# hackeeg-connector-12.net
KiCad netlist of a schematic drawn in EAGLE
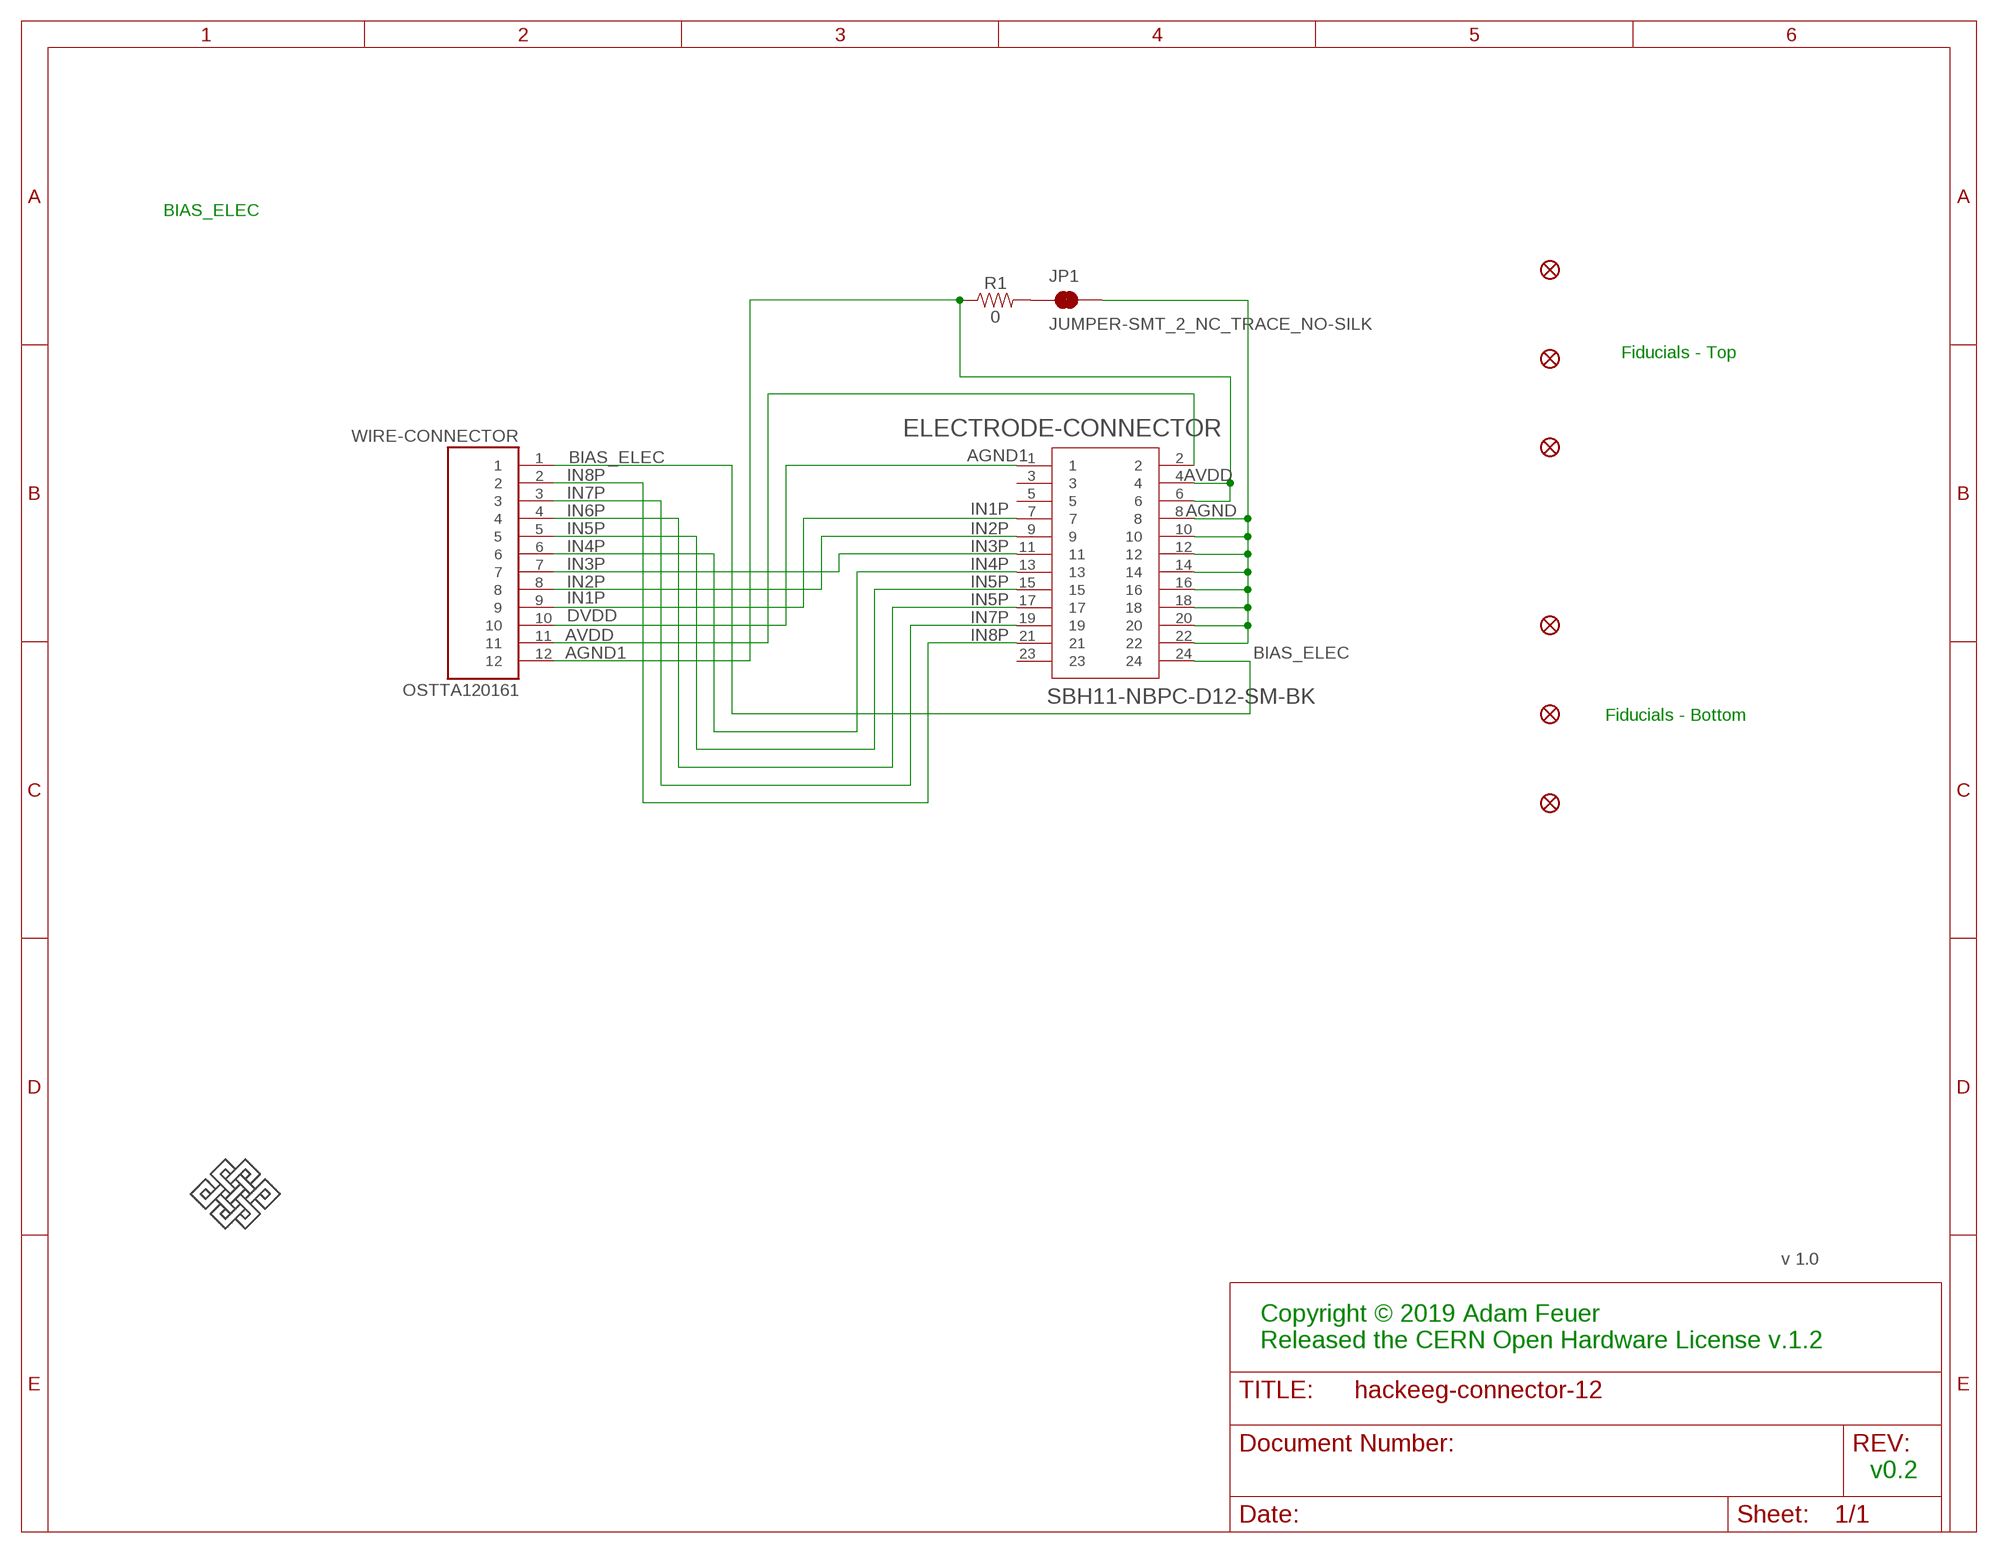
[diagram p0: schematic, sheet 1]

(export (version "E")
  (design (tool "Eeschema 10.0.6"))
  (components
    (comp (ref "ELECTRODE-CONNECTOR")
      (value "SBH11-NBPC-D12-SM-BK")
      (footprint "eagle-import:SULLINS_SBH11-NBPC-D12-SM-BK")
      (fields (field (name "MF") "Sullins Connector"))
      (libsource (lib "eagle-import") (part "SBH11-NBPC-D12-SM-BK"))
    )
    (comp (ref "FD1")
      (value "FIDUCIAL1X2")
      (footprint "eagle-import:FIDUCIAL-1X2")
      (libsource (lib "eagle-import") (part "FIDUCIAL1X2"))
    )
    (comp (ref "FD2")
      (value "FIDUCIAL1X2")
      (footprint "eagle-import:FIDUCIAL-1X2")
      (libsource (lib "eagle-import") (part "FIDUCIAL1X2"))
    )
    (comp (ref "FD3")
      (value "FIDUCIAL1X2")
      (footprint "eagle-import:FIDUCIAL-1X2")
      (libsource (lib "eagle-import") (part "FIDUCIAL1X2"))
    )
    (comp (ref "FD4")
      (value "FIDUCIAL1X2")
      (footprint "eagle-import:FIDUCIAL-1X2")
      (libsource (lib "eagle-import") (part "FIDUCIAL1X2"))
    )
    (comp (ref "FD5")
      (value "FIDUCIAL1X2")
      (footprint "eagle-import:FIDUCIAL-1X2")
      (libsource (lib "eagle-import") (part "FIDUCIAL1X2"))
    )
    (comp (ref "FD6")
      (value "FIDUCIAL1X2")
      (footprint "eagle-import:FIDUCIAL-1X2")
      (libsource (lib "eagle-import") (part "FIDUCIAL1X2"))
    )
    (comp (ref "JP1")
      (value "JUMPER-SMT_2_NC_TRACE_NO-SILK")
      (footprint "eagle-import:SMT-JUMPER_2_NC_TRACE_NO-SILK")
      (libsource (lib "eagle-import") (part "JUMPER-SMT_2_NC_TRACE_NO-SILK"))
    )
    (comp (ref "R1")
      (value "0")
      (footprint "eagle-import:0603")
      (libsource (lib "eagle-import") (part "0OHM-0603-1/10W-5%"))
    )
    (comp (ref "U$1")
      (value "ENDLESSKNOTENDLESSKNOT-MEDIUM")
      (footprint "eagle-import:ENDLESSKNOT-MEDIUM")
      (libsource (lib "eagle-import") (part "ENDLESSKNOTENDLESSKNOT-MEDIUM"))
    )
    (comp (ref "WIRE-CONNECTOR")
      (value "OSTTA120161")
      (footprint "eagle-import:ONSHORE_OSTTA120161")
      (fields (field (name "MF") "On Shore Technology Inc.") (field (name "MP") "OSTTA120161B"))
      (libsource (lib "eagle-import") (part "OSTTA120161"))
    )
  )
  (nets
    (net (code "1") (name "/AGND") (class "Default")
      (node (ref "ELECTRODE-CONNECTOR") (pin "10") (pinfunction "10_10") (pintype "passive"))
      (node (ref "ELECTRODE-CONNECTOR") (pin "12") (pinfunction "12_12") (pintype "passive"))
      (node (ref "ELECTRODE-CONNECTOR") (pin "14") (pinfunction "14_14") (pintype "passive"))
      (node (ref "ELECTRODE-CONNECTOR") (pin "16") (pinfunction "16_16") (pintype "passive"))
      (node (ref "ELECTRODE-CONNECTOR") (pin "18") (pinfunction "18_18") (pintype "passive"))
      (node (ref "ELECTRODE-CONNECTOR") (pin "20") (pinfunction "20_20") (pintype "passive"))
      (node (ref "ELECTRODE-CONNECTOR") (pin "22") (pinfunction "22_22") (pintype "passive"))
      (node (ref "ELECTRODE-CONNECTOR") (pin "8") (pinfunction "8_8") (pintype "passive"))
      (node (ref "JP1") (pin "2") (pinfunction "2_2") (pintype "passive"))
    )
    (net (code "2") (name "/AGND1") (class "Default")
      (node (ref "ELECTRODE-CONNECTOR") (pin "4") (pinfunction "4_4") (pintype "passive"))
      (node (ref "ELECTRODE-CONNECTOR") (pin "6") (pinfunction "6_6") (pintype "passive"))
      (node (ref "R1") (pin "1") (pinfunction "1_1") (pintype "passive"))
      (node (ref "WIRE-CONNECTOR") (pin "12") (pinfunction "12_12") (pintype "passive"))
    )
    (net (code "3") (name "/AVDD") (class "Default")
      (node (ref "ELECTRODE-CONNECTOR") (pin "2") (pinfunction "2_2") (pintype "passive"))
      (node (ref "WIRE-CONNECTOR") (pin "11") (pinfunction "11_11") (pintype "passive"))
    )
    (net (code "4") (name "/BIAS_ELEC") (class "Default")
      (node (ref "ELECTRODE-CONNECTOR") (pin "24") (pinfunction "24_24") (pintype "passive"))
      (node (ref "WIRE-CONNECTOR") (pin "1") (pinfunction "1_1") (pintype "passive"))
    )
    (net (code "5") (name "/DVDD") (class "Default")
      (node (ref "ELECTRODE-CONNECTOR") (pin "1") (pinfunction "1_1") (pintype "passive"))
      (node (ref "WIRE-CONNECTOR") (pin "10") (pinfunction "10_10") (pintype "passive"))
    )
    (net (code "6") (name "/IN1P") (class "Default")
      (node (ref "ELECTRODE-CONNECTOR") (pin "7") (pinfunction "7_7") (pintype "passive"))
      (node (ref "WIRE-CONNECTOR") (pin "9") (pinfunction "9_9") (pintype "passive"))
    )
    (net (code "7") (name "/IN2P") (class "Default")
      (node (ref "ELECTRODE-CONNECTOR") (pin "9") (pinfunction "9_9") (pintype "passive"))
      (node (ref "WIRE-CONNECTOR") (pin "8") (pinfunction "8_8") (pintype "passive"))
    )
    (net (code "8") (name "/IN3P") (class "Default")
      (node (ref "ELECTRODE-CONNECTOR") (pin "11") (pinfunction "11_11") (pintype "passive"))
      (node (ref "WIRE-CONNECTOR") (pin "7") (pinfunction "7_7") (pintype "passive"))
    )
    (net (code "9") (name "/IN4P") (class "Default")
      (node (ref "ELECTRODE-CONNECTOR") (pin "13") (pinfunction "13_13") (pintype "passive"))
      (node (ref "WIRE-CONNECTOR") (pin "6") (pinfunction "6_6") (pintype "passive"))
    )
    (net (code "10") (name "/IN5P") (class "Default")
      (node (ref "ELECTRODE-CONNECTOR") (pin "15") (pinfunction "15_15") (pintype "passive"))
      (node (ref "WIRE-CONNECTOR") (pin "5") (pinfunction "5_5") (pintype "passive"))
    )
    (net (code "11") (name "/IN6P") (class "Default")
      (node (ref "ELECTRODE-CONNECTOR") (pin "17") (pinfunction "17_17") (pintype "passive"))
      (node (ref "WIRE-CONNECTOR") (pin "4") (pinfunction "4_4") (pintype "passive"))
    )
    (net (code "12") (name "/IN7P") (class "Default")
      (node (ref "ELECTRODE-CONNECTOR") (pin "19") (pinfunction "19_19") (pintype "passive"))
      (node (ref "WIRE-CONNECTOR") (pin "3") (pinfunction "3_3") (pintype "passive"))
    )
    (net (code "13") (name "/IN8P") (class "Default")
      (node (ref "ELECTRODE-CONNECTOR") (pin "21") (pinfunction "21_21") (pintype "passive"))
      (node (ref "WIRE-CONNECTOR") (pin "2") (pinfunction "2_2") (pintype "passive"))
    )
    (net (code "14") (name "Net-(JP1-Pad1)") (class "Default")
      (node (ref "JP1") (pin "1") (pinfunction "1_1") (pintype "passive"))
      (node (ref "R1") (pin "2") (pinfunction "2_2") (pintype "passive"))
    )
    (net (code "15") (name "unconnected-(ELECTRODE-CONNECTOR-Pad3)") (class "Default")
      (node (ref "ELECTRODE-CONNECTOR") (pin "3") (pinfunction "3_3") (pintype "passive"))
    )
    (net (code "16") (name "unconnected-(ELECTRODE-CONNECTOR-Pad5)") (class "Default")
      (node (ref "ELECTRODE-CONNECTOR") (pin "5") (pinfunction "5_5") (pintype "passive"))
    )
    (net (code "17") (name "unconnected-(ELECTRODE-CONNECTOR-Pad23)") (class "Default")
      (node (ref "ELECTRODE-CONNECTOR") (pin "23") (pinfunction "23_23") (pintype "passive"))
    )
  )
)
